# Motor_Servo_Driver_Rev_G.net
KiCad netlist of a schematic drawn in EAGLE
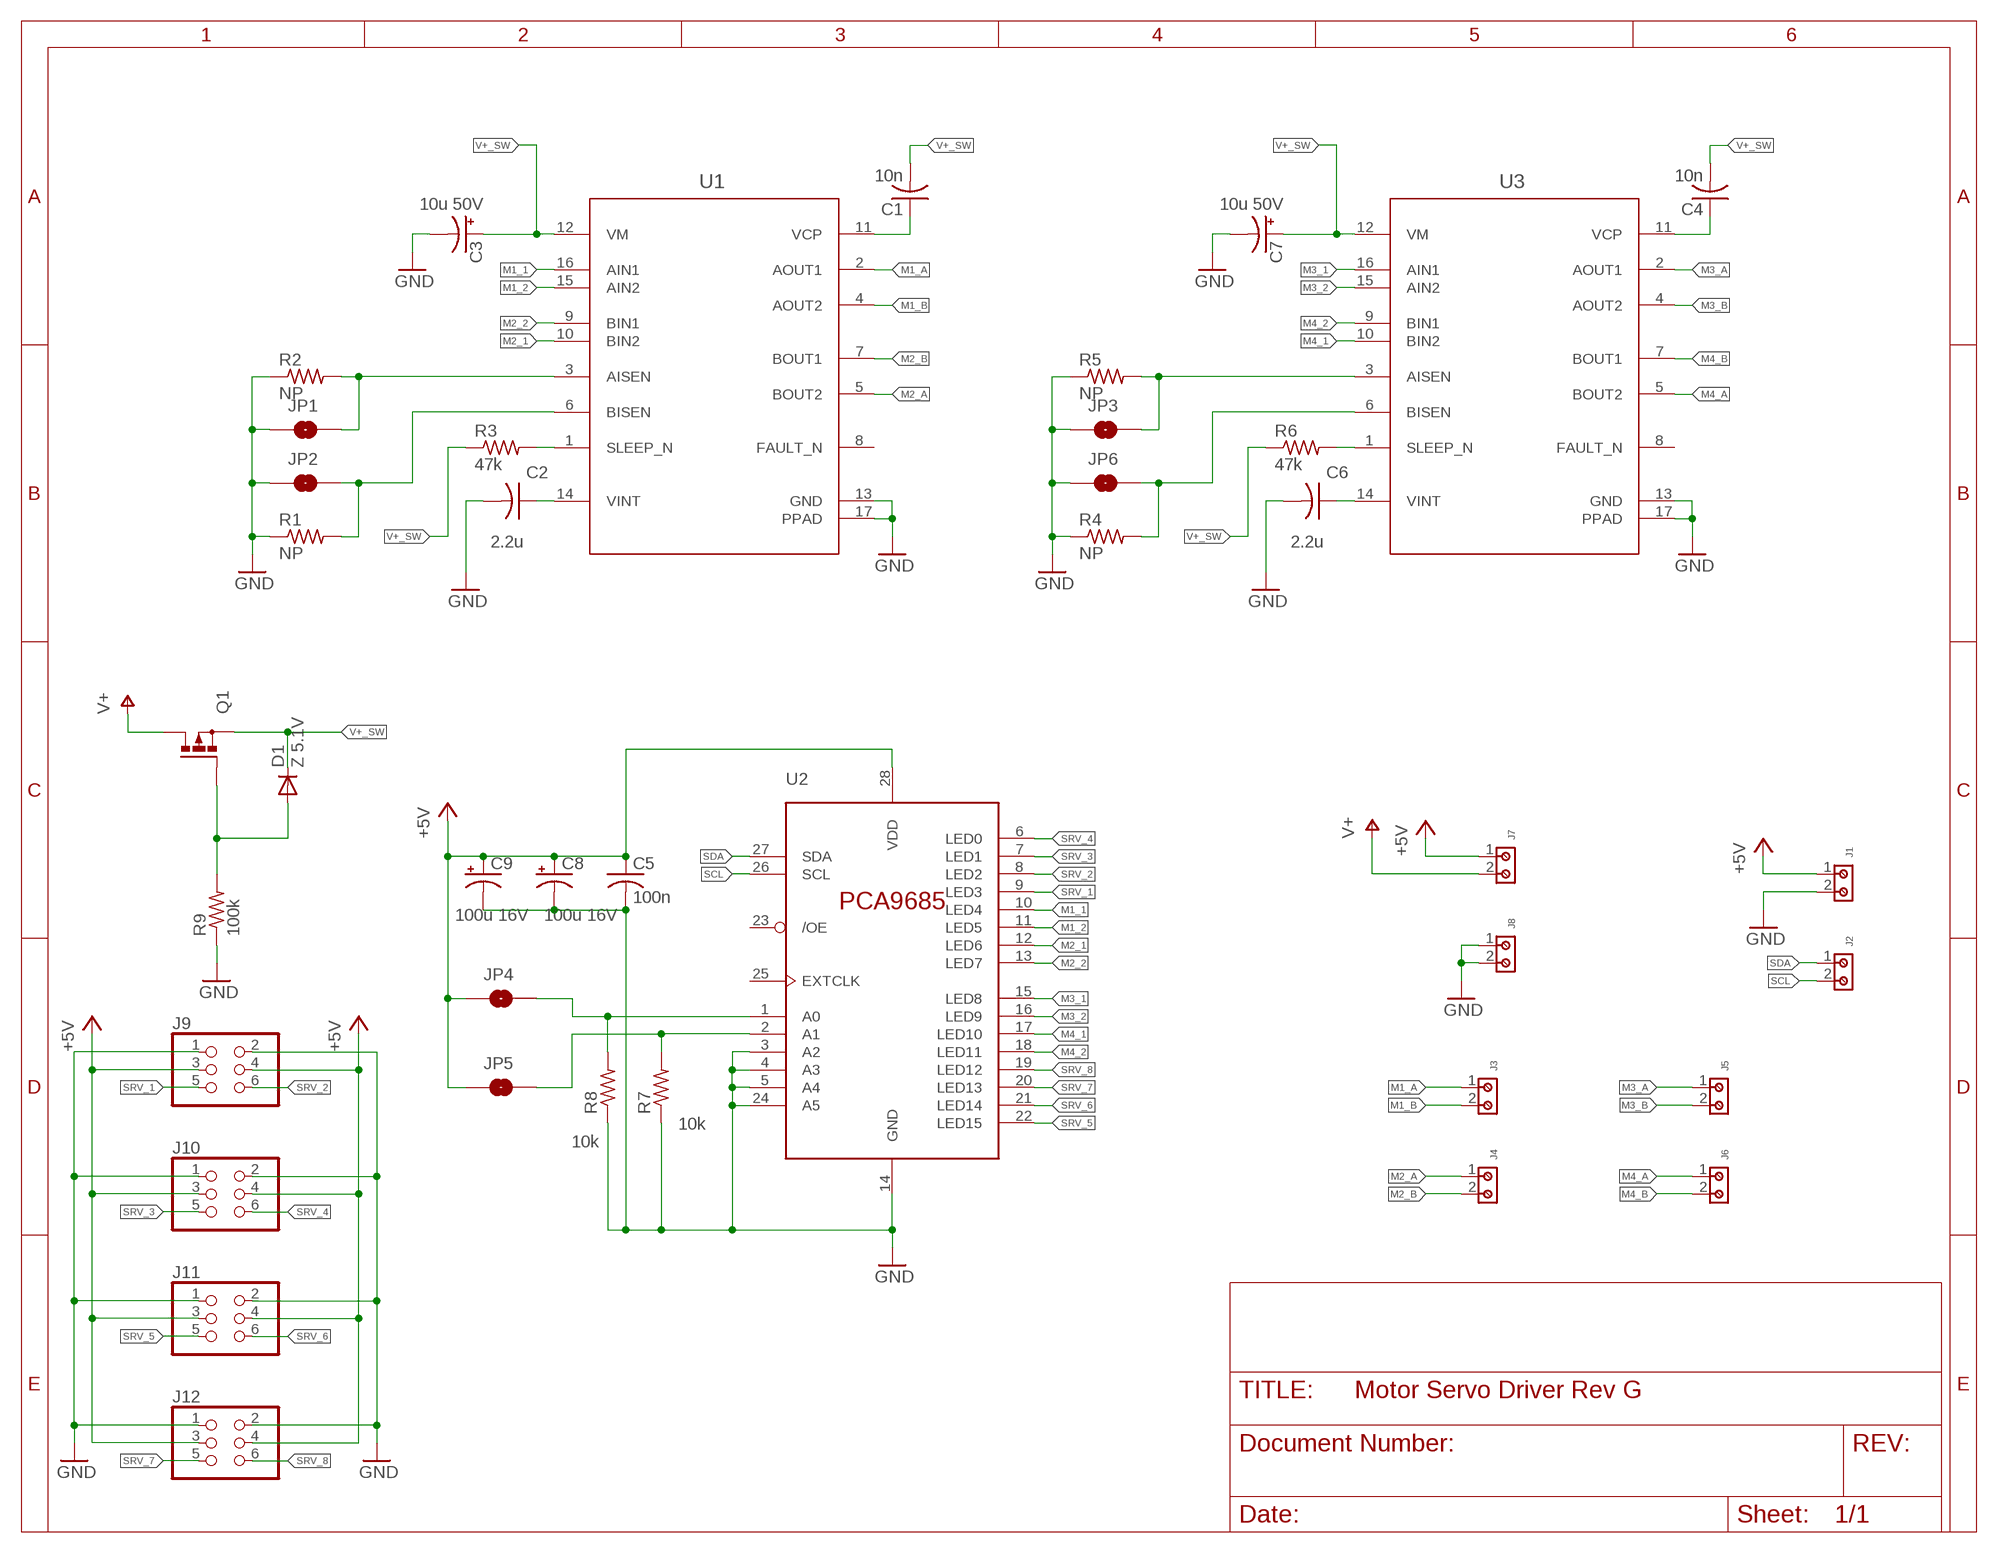
[diagram p0: schematic, sheet 1]

(export (version "E")
  (design (tool "Eeschema 10.0.6"))
  (components
    (comp (ref "C1")
      (value "10n")
      (footprint "eagle-import:C050-024X044")
      (libsource (lib "eagle-import") (part "CAPACITOR-CERAMIC"))
    )
    (comp (ref "C2")
      (value "2.2u")
      (footprint "eagle-import:C050-024X044")
      (libsource (lib "eagle-import") (part "CAPACITOR-CERAMIC"))
    )
    (comp (ref "C3")
      (value "10u 50V")
      (footprint "eagle-import:E2,5-5")
      (libsource (lib "eagle-import") (part "ELECTROLYTIC-CAPACITOR2.5-5"))
    )
    (comp (ref "C4")
      (value "10n")
      (footprint "eagle-import:C050-024X044")
      (libsource (lib "eagle-import") (part "CAPACITOR-CERAMIC"))
    )
    (comp (ref "C5")
      (value "100n")
      (footprint "eagle-import:C050-024X044")
      (libsource (lib "eagle-import") (part "CAPACITOR-CERAMIC"))
    )
    (comp (ref "C6")
      (value "2.2u")
      (footprint "eagle-import:C050-024X044")
      (libsource (lib "eagle-import") (part "CAPACITOR-CERAMIC"))
    )
    (comp (ref "C7")
      (value "10u 50V")
      (footprint "eagle-import:E2,5-5")
      (libsource (lib "eagle-import") (part "ELECTROLYTIC-CAPACITOR2.5-5"))
    )
    (comp (ref "C8")
      (value "100u 16V")
      (footprint "eagle-import:E2,5-5")
      (libsource (lib "eagle-import") (part "ELECTROLYTIC-CAPACITOR2.5-5"))
    )
    (comp (ref "C9")
      (value "100u 16V")
      (footprint "eagle-import:E2,5-5")
      (libsource (lib "eagle-import") (part "ELECTROLYTIC-CAPACITOR2.5-5"))
    )
    (comp (ref "D1")
      (value "Z 5.1V")
      (footprint "eagle-import:DO41-10")
      (libsource (lib "eagle-import") (part "1N4000"))
    )
    (comp (ref "J1")
      (value "691214110002")
      (footprint "eagle-import:691214110002")
      (libsource (lib "eagle-import") (part "691214110002"))
    )
    (comp (ref "J2")
      (value "691214110002")
      (footprint "eagle-import:691214110002")
      (libsource (lib "eagle-import") (part "691214110002"))
    )
    (comp (ref "J3")
      (value "691214110002")
      (footprint "eagle-import:691214110002")
      (libsource (lib "eagle-import") (part "691214110002"))
    )
    (comp (ref "J4")
      (value "691214110002")
      (footprint "eagle-import:691214110002")
      (libsource (lib "eagle-import") (part "691214110002"))
    )
    (comp (ref "J5")
      (value "691214110002")
      (footprint "eagle-import:691214110002")
      (libsource (lib "eagle-import") (part "691214110002"))
    )
    (comp (ref "J6")
      (value "691214110002")
      (footprint "eagle-import:691214110002")
      (libsource (lib "eagle-import") (part "691214110002"))
    )
    (comp (ref "J7")
      (value "691214110002")
      (footprint "eagle-import:691214110002")
      (libsource (lib "eagle-import") (part "691214110002"))
    )
    (comp (ref "J8")
      (value "691214110002")
      (footprint "eagle-import:691214110002")
      (libsource (lib "eagle-import") (part "691214110002"))
    )
    (comp (ref "J9")
      (value "PINHD-2X3")
      (footprint "eagle-import:2X03")
      (libsource (lib "eagle-import") (part "PINHD-2X3"))
    )
    (comp (ref "J10")
      (value "PINHD-2X3")
      (footprint "eagle-import:2X03")
      (libsource (lib "eagle-import") (part "PINHD-2X3"))
    )
    (comp (ref "J11")
      (value "PINHD-2X3")
      (footprint "eagle-import:2X03")
      (libsource (lib "eagle-import") (part "PINHD-2X3"))
    )
    (comp (ref "J12")
      (value "PINHD-2X3")
      (footprint "eagle-import:2X03")
      (libsource (lib "eagle-import") (part "PINHD-2X3"))
    )
    (comp (ref "JP1")
      (value "JUMPER-SMT_2_NO_SILK")
      (footprint "eagle-import:SMT-JUMPER_2_NO_SILK")
      (libsource (lib "eagle-import") (part "JUMPER-SMT_2_NO_SILK"))
    )
    (comp (ref "JP2")
      (value "JUMPER-SMT_2_NO_SILK")
      (footprint "eagle-import:SMT-JUMPER_2_NO_SILK")
      (libsource (lib "eagle-import") (part "JUMPER-SMT_2_NO_SILK"))
    )
    (comp (ref "JP3")
      (value "JUMPER-SMT_2_NO_SILK")
      (footprint "eagle-import:SMT-JUMPER_2_NO_SILK")
      (libsource (lib "eagle-import") (part "JUMPER-SMT_2_NO_SILK"))
    )
    (comp (ref "JP4")
      (value "JUMPER-SMT_2_NO_SILK")
      (footprint "eagle-import:SMT-JUMPER_2_NO_SILK")
      (libsource (lib "eagle-import") (part "JUMPER-SMT_2_NO_SILK"))
    )
    (comp (ref "JP5")
      (value "JUMPER-SMT_2_NO_SILK")
      (footprint "eagle-import:SMT-JUMPER_2_NO_SILK")
      (libsource (lib "eagle-import") (part "JUMPER-SMT_2_NO_SILK"))
    )
    (comp (ref "JP6")
      (value "JUMPER-SMT_2_NO_SILK")
      (footprint "eagle-import:SMT-JUMPER_2_NO_SILK")
      (libsource (lib "eagle-import") (part "JUMPER-SMT_2_NO_SILK"))
    )
    (comp (ref "Q1")
      (value "PMOSFET_PTO220BV")
      (footprint "eagle-import:TO220BV")
      (libsource (lib "eagle-import") (part "PMOSFET_PTO220BV"))
    )
    (comp (ref "R1")
      (value "NP")
      (footprint "eagle-import:R1206")
      (libsource (lib "eagle-import") (part "R-US_R1206"))
    )
    (comp (ref "R2")
      (value "NP")
      (footprint "eagle-import:R1206")
      (libsource (lib "eagle-import") (part "R-US_R1206"))
    )
    (comp (ref "R3")
      (value "47k")
      (footprint "eagle-import:0207_10")
      (libsource (lib "eagle-import") (part "RESISTOR"))
    )
    (comp (ref "R4")
      (value "NP")
      (footprint "eagle-import:R1206")
      (libsource (lib "eagle-import") (part "R-US_R1206"))
    )
    (comp (ref "R5")
      (value "NP")
      (footprint "eagle-import:R1206")
      (libsource (lib "eagle-import") (part "R-US_R1206"))
    )
    (comp (ref "R6")
      (value "47k")
      (footprint "eagle-import:0207_10")
      (libsource (lib "eagle-import") (part "RESISTOR"))
    )
    (comp (ref "R7")
      (value "10k")
      (footprint "eagle-import:0207_10")
      (libsource (lib "eagle-import") (part "RESISTOR"))
    )
    (comp (ref "R8")
      (value "10k")
      (footprint "eagle-import:0207_10")
      (libsource (lib "eagle-import") (part "RESISTOR"))
    )
    (comp (ref "R9")
      (value "100k")
      (footprint "eagle-import:0207_10")
      (libsource (lib "eagle-import") (part "RESISTOR"))
    )
    (comp (ref "U1")
      (value "Value")
      (footprint "eagle-import:PWP0016C_N")
      (fields (field (name "MANUFACTURER") "Texas Instruments") (field (name "PARTNUMBER") "DRV8833PWPR"))
      (libsource (lib "eagle-import") (part "DRV8833PWP"))
    )
    (comp (ref "U2")
      (value "PCA9685")
      (footprint "eagle-import:TSSOP28")
      (libsource (lib "eagle-import") (part "PCA9685"))
    )
    (comp (ref "U3")
      (value "Value")
      (footprint "eagle-import:PWP0016C_N")
      (fields (field (name "MANUFACTURER") "Texas Instruments") (field (name "PARTNUMBER") "DRV8833PWPR"))
      (libsource (lib "eagle-import") (part "DRV8833PWP"))
    )
  )
  (nets
    (net (code "1") (name "+5V") (class "Default")
      (node (ref "C5") (pin "1") (pinfunction "1_1") (pintype "passive"))
      (node (ref "C8") (pin "+") (pinfunction "+_+") (pintype "passive"))
      (node (ref "C9") (pin "+") (pinfunction "+_+") (pintype "passive"))
      (node (ref "J1") (pin "1") (pinfunction "1_1") (pintype "passive"))
      (node (ref "J10") (pin "3") (pinfunction "3_3") (pintype "passive"))
      (node (ref "J10") (pin "4") (pinfunction "4_4") (pintype "passive"))
      (node (ref "J11") (pin "3") (pinfunction "3_3") (pintype "passive"))
      (node (ref "J11") (pin "4") (pinfunction "4_4") (pintype "passive"))
      (node (ref "J12") (pin "3") (pinfunction "3_3") (pintype "passive"))
      (node (ref "J12") (pin "4") (pinfunction "4_4") (pintype "passive"))
      (node (ref "J7") (pin "1") (pinfunction "1_1") (pintype "passive"))
      (node (ref "J9") (pin "3") (pinfunction "3_3") (pintype "passive"))
      (node (ref "J9") (pin "4") (pinfunction "4_4") (pintype "passive"))
      (node (ref "JP4") (pin "1") (pinfunction "1_1") (pintype "passive"))
      (node (ref "JP5") (pin "1") (pinfunction "1_1") (pintype "passive"))
      (node (ref "U2") (pin "28") (pinfunction "VDD_28") (pintype "power_in"))
    )
    (net (code "2") (name "GND") (class "Default")
      (node (ref "C2") (pin "2") (pinfunction "2_2") (pintype "passive"))
      (node (ref "C3") (pin "-") (pinfunction "-_-") (pintype "passive"))
      (node (ref "C5") (pin "2") (pinfunction "2_2") (pintype "passive"))
      (node (ref "C6") (pin "2") (pinfunction "2_2") (pintype "passive"))
      (node (ref "C7") (pin "-") (pinfunction "-_-") (pintype "passive"))
      (node (ref "C8") (pin "-") (pinfunction "-_-") (pintype "passive"))
      (node (ref "C9") (pin "-") (pinfunction "-_-") (pintype "passive"))
      (node (ref "J1") (pin "2") (pinfunction "2_2") (pintype "passive"))
      (node (ref "J10") (pin "1") (pinfunction "1_1") (pintype "passive"))
      (node (ref "J10") (pin "2") (pinfunction "2_2") (pintype "passive"))
      (node (ref "J11") (pin "1") (pinfunction "1_1") (pintype "passive"))
      (node (ref "J11") (pin "2") (pinfunction "2_2") (pintype "passive"))
      (node (ref "J12") (pin "1") (pinfunction "1_1") (pintype "passive"))
      (node (ref "J12") (pin "2") (pinfunction "2_2") (pintype "passive"))
      (node (ref "J8") (pin "1") (pinfunction "1_1") (pintype "passive"))
      (node (ref "J8") (pin "2") (pinfunction "2_2") (pintype "passive"))
      (node (ref "J9") (pin "1") (pinfunction "1_1") (pintype "passive"))
      (node (ref "J9") (pin "2") (pinfunction "2_2") (pintype "passive"))
      (node (ref "JP1") (pin "1") (pinfunction "1_1") (pintype "passive"))
      (node (ref "JP2") (pin "1") (pinfunction "1_1") (pintype "passive"))
      (node (ref "JP3") (pin "1") (pinfunction "1_1") (pintype "passive"))
      (node (ref "JP6") (pin "1") (pinfunction "1_1") (pintype "passive"))
      (node (ref "R1") (pin "1") (pinfunction "1_1") (pintype "passive"))
      (node (ref "R2") (pin "1") (pinfunction "1_1") (pintype "passive"))
      (node (ref "R4") (pin "1") (pinfunction "1_1") (pintype "passive"))
      (node (ref "R5") (pin "1") (pinfunction "1_1") (pintype "passive"))
      (node (ref "R7") (pin "1") (pinfunction "1_1") (pintype "passive"))
      (node (ref "R8") (pin "1") (pinfunction "1_1") (pintype "passive"))
      (node (ref "R9") (pin "1") (pinfunction "1_1") (pintype "passive"))
      (node (ref "U1") (pin "13") (pinfunction "GND_13") (pintype "power_in"))
      (node (ref "U1") (pin "17") (pinfunction "PPAD_17") (pintype "power_in"))
      (node (ref "U2") (pin "14") (pinfunction "GND_14") (pintype "power_in"))
      (node (ref "U2") (pin "24") (pinfunction "A5_24") (pintype "bidirectional"))
      (node (ref "U2") (pin "3") (pinfunction "A2_3") (pintype "bidirectional"))
      (node (ref "U2") (pin "4") (pinfunction "A3_4") (pintype "bidirectional"))
      (node (ref "U2") (pin "5") (pinfunction "A4_5") (pintype "bidirectional"))
      (node (ref "U3") (pin "13") (pinfunction "GND_13") (pintype "power_in"))
      (node (ref "U3") (pin "17") (pinfunction "PPAD_17") (pintype "power_in"))
    )
    (net (code "3") (name "M1_1") (class "Default")
      (node (ref "U1") (pin "16") (pinfunction "AIN1_16") (pintype "input"))
      (node (ref "U2") (pin "10") (pinfunction "LED4_10") (pintype "bidirectional"))
    )
    (net (code "4") (name "M1_2") (class "Default")
      (node (ref "U1") (pin "15") (pinfunction "AIN2_15") (pintype "input"))
      (node (ref "U2") (pin "11") (pinfunction "LED5_11") (pintype "bidirectional"))
    )
    (net (code "5") (name "M1_A") (class "Default")
      (node (ref "J3") (pin "1") (pinfunction "1_1") (pintype "passive"))
      (node (ref "U1") (pin "2") (pinfunction "AOUT1_2") (pintype "tri_state"))
    )
    (net (code "6") (name "M1_B") (class "Default")
      (node (ref "J3") (pin "2") (pinfunction "2_2") (pintype "passive"))
      (node (ref "U1") (pin "4") (pinfunction "AOUT2_4") (pintype "tri_state"))
    )
    (net (code "7") (name "M2_1") (class "Default")
      (node (ref "U1") (pin "10") (pinfunction "BIN2_10") (pintype "input"))
      (node (ref "U2") (pin "12") (pinfunction "LED6_12") (pintype "bidirectional"))
    )
    (net (code "8") (name "M2_2") (class "Default")
      (node (ref "U1") (pin "9") (pinfunction "BIN1_9") (pintype "input"))
      (node (ref "U2") (pin "13") (pinfunction "LED7_13") (pintype "bidirectional"))
    )
    (net (code "9") (name "M2_A") (class "Default")
      (node (ref "J4") (pin "1") (pinfunction "1_1") (pintype "passive"))
      (node (ref "U1") (pin "5") (pinfunction "BOUT2_5") (pintype "tri_state"))
    )
    (net (code "10") (name "M2_B") (class "Default")
      (node (ref "J4") (pin "2") (pinfunction "2_2") (pintype "passive"))
      (node (ref "U1") (pin "7") (pinfunction "BOUT1_7") (pintype "tri_state"))
    )
    (net (code "11") (name "M3_1") (class "Default")
      (node (ref "U2") (pin "15") (pinfunction "LED8_15") (pintype "bidirectional"))
      (node (ref "U3") (pin "16") (pinfunction "AIN1_16") (pintype "input"))
    )
    (net (code "12") (name "M3_2") (class "Default")
      (node (ref "U2") (pin "16") (pinfunction "LED9_16") (pintype "bidirectional"))
      (node (ref "U3") (pin "15") (pinfunction "AIN2_15") (pintype "input"))
    )
    (net (code "13") (name "M3_A") (class "Default")
      (node (ref "J5") (pin "1") (pinfunction "1_1") (pintype "passive"))
      (node (ref "U3") (pin "2") (pinfunction "AOUT1_2") (pintype "tri_state"))
    )
    (net (code "14") (name "M3_B") (class "Default")
      (node (ref "J5") (pin "2") (pinfunction "2_2") (pintype "passive"))
      (node (ref "U3") (pin "4") (pinfunction "AOUT2_4") (pintype "tri_state"))
    )
    (net (code "15") (name "M4_1") (class "Default")
      (node (ref "U2") (pin "17") (pinfunction "LED10_17") (pintype "bidirectional"))
      (node (ref "U3") (pin "10") (pinfunction "BIN2_10") (pintype "input"))
    )
    (net (code "16") (name "M4_2") (class "Default")
      (node (ref "U2") (pin "18") (pinfunction "LED11_18") (pintype "bidirectional"))
      (node (ref "U3") (pin "9") (pinfunction "BIN1_9") (pintype "input"))
    )
    (net (code "17") (name "M4_A") (class "Default")
      (node (ref "J6") (pin "1") (pinfunction "1_1") (pintype "passive"))
      (node (ref "U3") (pin "5") (pinfunction "BOUT2_5") (pintype "tri_state"))
    )
    (net (code "18") (name "M4_B") (class "Default")
      (node (ref "J6") (pin "2") (pinfunction "2_2") (pintype "passive"))
      (node (ref "U3") (pin "7") (pinfunction "BOUT1_7") (pintype "tri_state"))
    )
    (net (code "19") (name "Net-(D1-PadA)") (class "Default")
      (node (ref "D1") (pin "A") (pinfunction "A_A") (pintype "passive"))
      (node (ref "Q1") (pin "G") (pinfunction "G_G") (pintype "passive"))
      (node (ref "R9") (pin "2") (pinfunction "2_2") (pintype "passive"))
    )
    (net (code "20") (name "Net-(U1-AISEN)") (class "Default")
      (node (ref "JP1") (pin "2") (pinfunction "2_2") (pintype "passive"))
      (node (ref "R2") (pin "2") (pinfunction "2_2") (pintype "passive"))
      (node (ref "U1") (pin "3") (pinfunction "AISEN_3") (pintype "input"))
    )
    (net (code "21") (name "Net-(U1-BISEN)") (class "Default")
      (node (ref "JP2") (pin "2") (pinfunction "2_2") (pintype "passive"))
      (node (ref "R1") (pin "2") (pinfunction "2_2") (pintype "passive"))
      (node (ref "U1") (pin "6") (pinfunction "BISEN_6") (pintype "input"))
    )
    (net (code "22") (name "Net-(U1-SLEEP_N)") (class "Default")
      (node (ref "R3") (pin "2") (pinfunction "2_2") (pintype "passive"))
      (node (ref "U1") (pin "1") (pinfunction "SLEEP_N_1") (pintype "input"))
    )
    (net (code "23") (name "Net-(U1-VCP)") (class "Default")
      (node (ref "C1") (pin "1") (pinfunction "1_1") (pintype "passive"))
      (node (ref "U1") (pin "11") (pinfunction "VCP_11") (pintype "bidirectional"))
    )
    (net (code "24") (name "Net-(U1-VINT)") (class "Default")
      (node (ref "C2") (pin "1") (pinfunction "1_1") (pintype "passive"))
      (node (ref "U1") (pin "14") (pinfunction "VINT_14") (pintype "passive"))
    )
    (net (code "25") (name "Net-(U2-A0)") (class "Default")
      (node (ref "JP4") (pin "2") (pinfunction "2_2") (pintype "passive"))
      (node (ref "R8") (pin "2") (pinfunction "2_2") (pintype "passive"))
      (node (ref "U2") (pin "1") (pinfunction "A0_1") (pintype "bidirectional"))
    )
    (net (code "26") (name "Net-(U2-A1)") (class "Default")
      (node (ref "JP5") (pin "2") (pinfunction "2_2") (pintype "passive"))
      (node (ref "R7") (pin "2") (pinfunction "2_2") (pintype "passive"))
      (node (ref "U2") (pin "2") (pinfunction "A1_2") (pintype "bidirectional"))
    )
    (net (code "27") (name "Net-(U3-AISEN)") (class "Default")
      (node (ref "JP3") (pin "2") (pinfunction "2_2") (pintype "passive"))
      (node (ref "R5") (pin "2") (pinfunction "2_2") (pintype "passive"))
      (node (ref "U3") (pin "3") (pinfunction "AISEN_3") (pintype "input"))
    )
    (net (code "28") (name "Net-(U3-BISEN)") (class "Default")
      (node (ref "JP6") (pin "2") (pinfunction "2_2") (pintype "passive"))
      (node (ref "R4") (pin "2") (pinfunction "2_2") (pintype "passive"))
      (node (ref "U3") (pin "6") (pinfunction "BISEN_6") (pintype "input"))
    )
    (net (code "29") (name "Net-(U3-SLEEP_N)") (class "Default")
      (node (ref "R6") (pin "2") (pinfunction "2_2") (pintype "passive"))
      (node (ref "U3") (pin "1") (pinfunction "SLEEP_N_1") (pintype "input"))
    )
    (net (code "30") (name "Net-(U3-VCP)") (class "Default")
      (node (ref "C4") (pin "1") (pinfunction "1_1") (pintype "passive"))
      (node (ref "U3") (pin "11") (pinfunction "VCP_11") (pintype "bidirectional"))
    )
    (net (code "31") (name "Net-(U3-VINT)") (class "Default")
      (node (ref "C6") (pin "1") (pinfunction "1_1") (pintype "passive"))
      (node (ref "U3") (pin "14") (pinfunction "VINT_14") (pintype "passive"))
    )
    (net (code "32") (name "SCL") (class "Default")
      (node (ref "J2") (pin "2") (pinfunction "2_2") (pintype "passive"))
      (node (ref "U2") (pin "26") (pinfunction "SCL_26") (pintype "bidirectional"))
    )
    (net (code "33") (name "SDA") (class "Default")
      (node (ref "J2") (pin "1") (pinfunction "1_1") (pintype "passive"))
      (node (ref "U2") (pin "27") (pinfunction "SDA_27") (pintype "bidirectional"))
    )
    (net (code "34") (name "SRV_1") (class "Default")
      (node (ref "J9") (pin "5") (pinfunction "5_5") (pintype "passive"))
      (node (ref "U2") (pin "9") (pinfunction "LED3_9") (pintype "bidirectional"))
    )
    (net (code "35") (name "SRV_2") (class "Default")
      (node (ref "J9") (pin "6") (pinfunction "6_6") (pintype "passive"))
      (node (ref "U2") (pin "8") (pinfunction "LED2_8") (pintype "bidirectional"))
    )
    (net (code "36") (name "SRV_3") (class "Default")
      (node (ref "J10") (pin "5") (pinfunction "5_5") (pintype "passive"))
      (node (ref "U2") (pin "7") (pinfunction "LED1_7") (pintype "bidirectional"))
    )
    (net (code "37") (name "SRV_4") (class "Default")
      (node (ref "J10") (pin "6") (pinfunction "6_6") (pintype "passive"))
      (node (ref "U2") (pin "6") (pinfunction "LED0_6") (pintype "bidirectional"))
    )
    (net (code "38") (name "SRV_5") (class "Default")
      (node (ref "J11") (pin "5") (pinfunction "5_5") (pintype "passive"))
      (node (ref "U2") (pin "22") (pinfunction "LED15_22") (pintype "bidirectional"))
    )
    (net (code "39") (name "SRV_6") (class "Default")
      (node (ref "J11") (pin "6") (pinfunction "6_6") (pintype "passive"))
      (node (ref "U2") (pin "21") (pinfunction "LED14_21") (pintype "bidirectional"))
    )
    (net (code "40") (name "SRV_7") (class "Default")
      (node (ref "J12") (pin "5") (pinfunction "5_5") (pintype "passive"))
      (node (ref "U2") (pin "20") (pinfunction "LED13_20") (pintype "bidirectional"))
    )
    (net (code "41") (name "SRV_8") (class "Default")
      (node (ref "J12") (pin "6") (pinfunction "6_6") (pintype "passive"))
      (node (ref "U2") (pin "19") (pinfunction "LED12_19") (pintype "bidirectional"))
    )
    (net (code "42") (name "V+") (class "Default")
      (node (ref "J7") (pin "2") (pinfunction "2_2") (pintype "passive"))
      (node (ref "Q1") (pin "D") (pinfunction "D_D") (pintype "passive"))
    )
    (net (code "43") (name "V+_SW") (class "Default")
      (node (ref "C1") (pin "2") (pinfunction "2_2") (pintype "passive"))
      (node (ref "C3") (pin "+") (pinfunction "+_+") (pintype "passive"))
      (node (ref "C4") (pin "2") (pinfunction "2_2") (pintype "passive"))
      (node (ref "C7") (pin "+") (pinfunction "+_+") (pintype "passive"))
      (node (ref "D1") (pin "C") (pinfunction "C_C") (pintype "passive"))
      (node (ref "Q1") (pin "S") (pinfunction "S_S") (pintype "passive"))
      (node (ref "R3") (pin "1") (pinfunction "1_1") (pintype "passive"))
      (node (ref "R6") (pin "1") (pinfunction "1_1") (pintype "passive"))
      (node (ref "U1") (pin "12") (pinfunction "VM_12") (pintype "power_in"))
      (node (ref "U3") (pin "12") (pinfunction "VM_12") (pintype "power_in"))
    )
    (net (code "44") (name "unconnected-(U1-FAULT_N-Pad8)") (class "Default")
      (node (ref "U1") (pin "8") (pinfunction "FAULT_N_8") (pintype "open_collector"))
    )
    (net (code "45") (name "unconnected-(U2-EXTCLK-Pad25)") (class "Default")
      (node (ref "U2") (pin "25") (pinfunction "EXTCLK_25") (pintype "input"))
    )
    (net (code "46") (name "unconnected-(U2-{slash}OE-Pad23)") (class "Default")
      (node (ref "U2") (pin "23") (pinfunction "/OE_23") (pintype "bidirectional"))
    )
    (net (code "47") (name "unconnected-(U3-FAULT_N-Pad8)") (class "Default")
      (node (ref "U3") (pin "8") (pinfunction "FAULT_N_8") (pintype "open_collector"))
    )
  )
)
